# SAM3X-MCU.net
KiCad netlist of a schematic drawn in Altium Designer
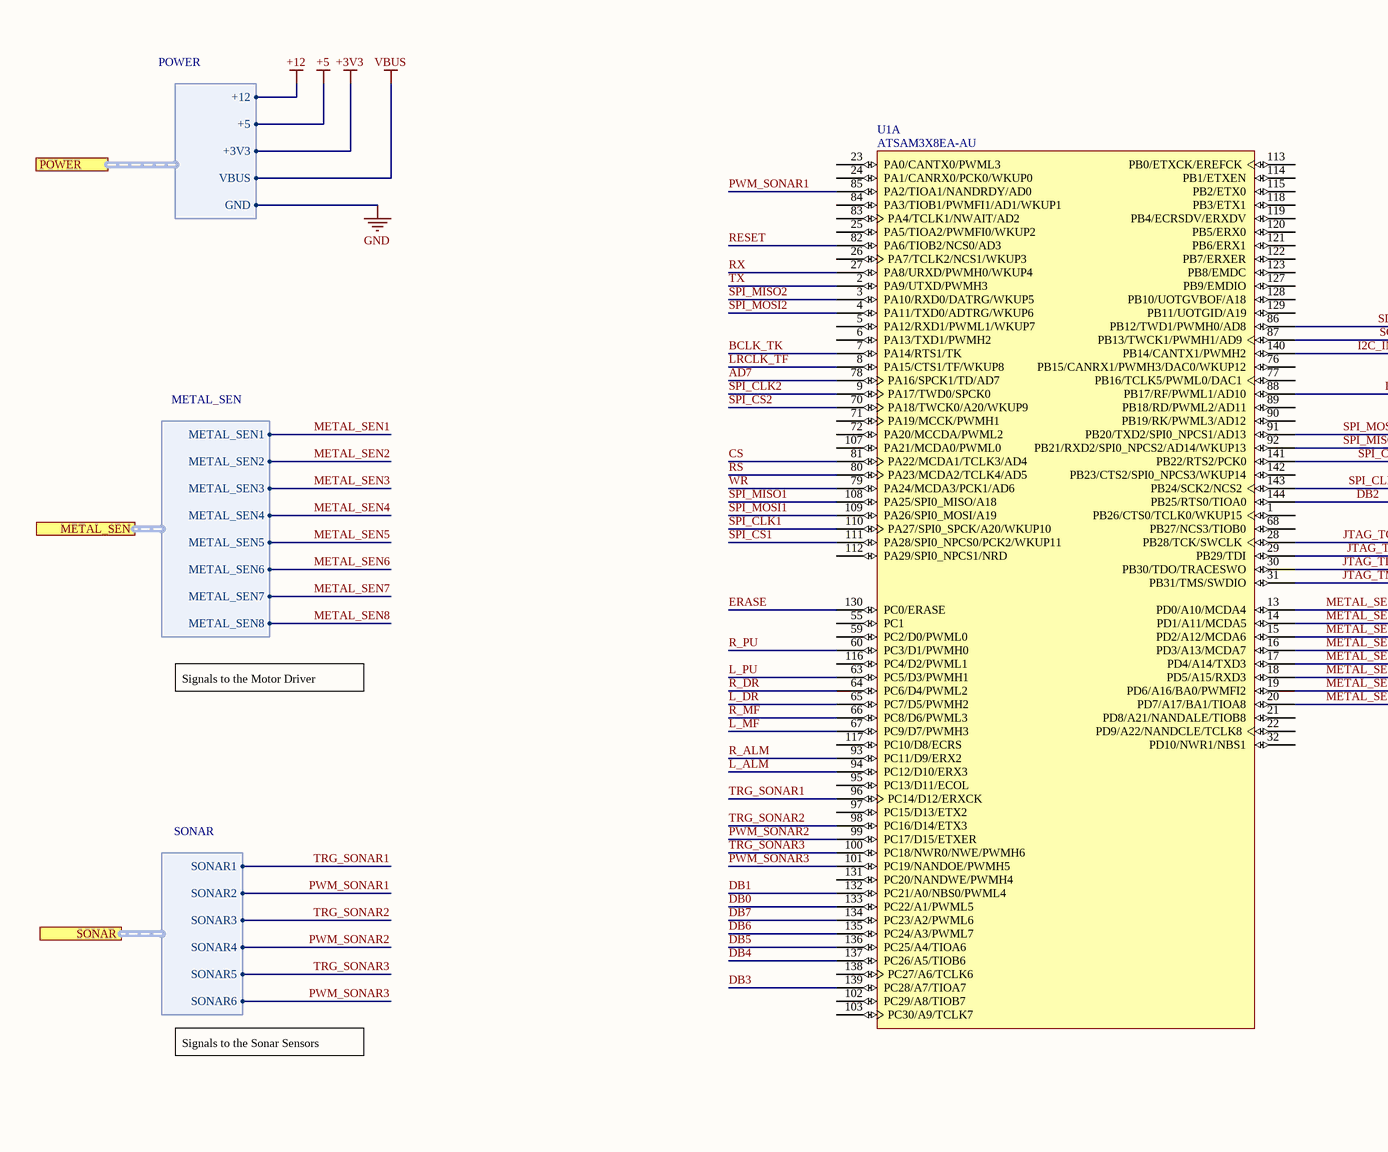
[diagram p0: SAM3X-MCU.SchDoc, left]
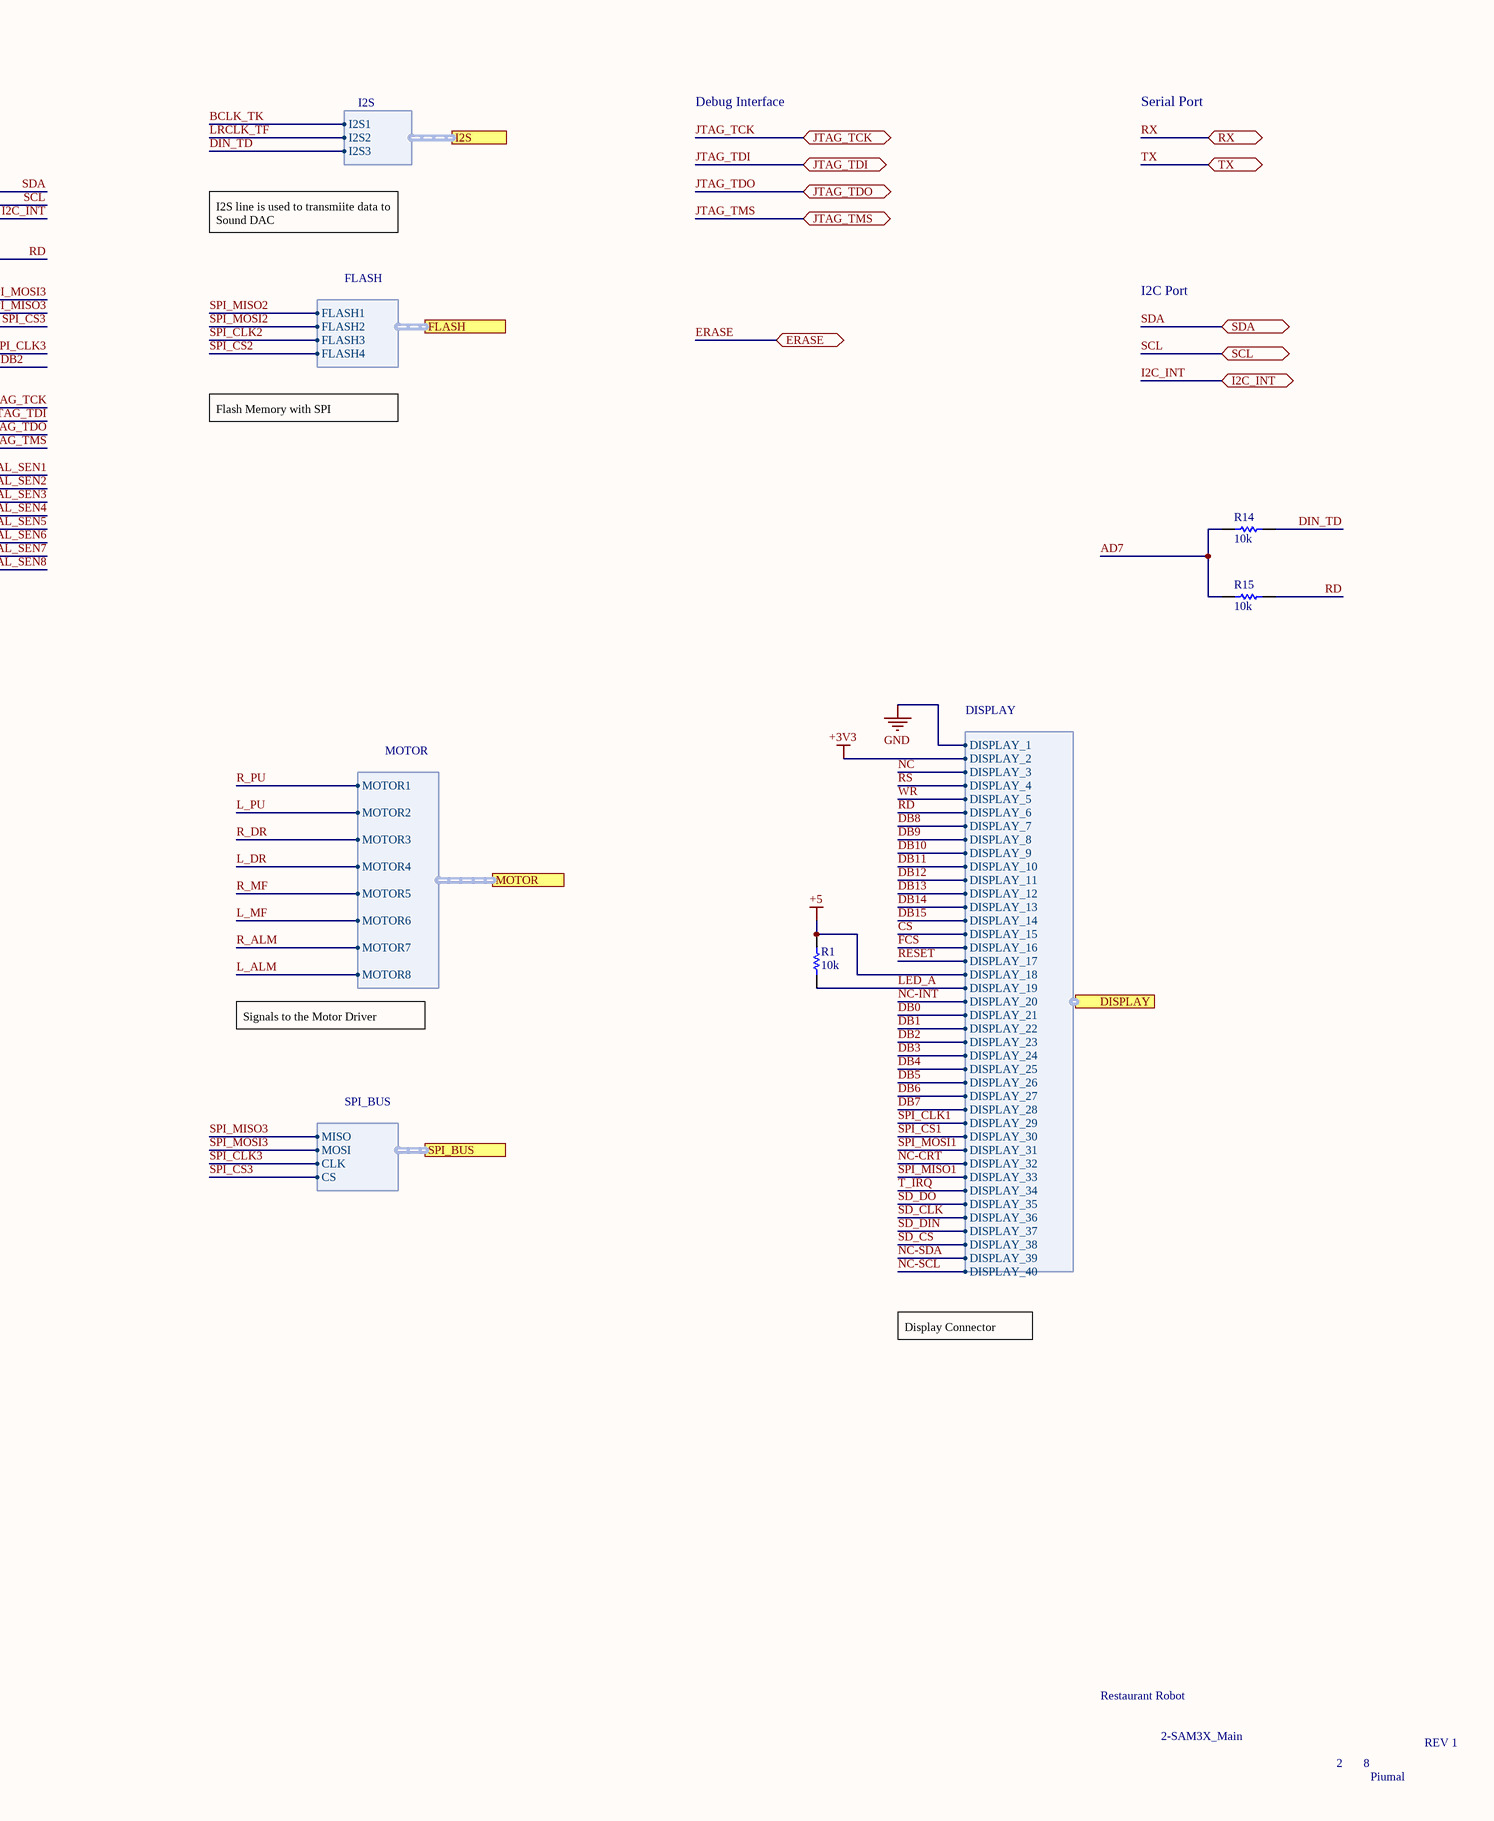
[diagram p1: SAM3X-MCU.SchDoc, right]

(export (version "E")
  (design (tool "Eeschema 10.0.6"))
  (components
    (comp (ref "R1")
      (value "RC0805JR-0710KL")
      (footprint "RESC2013X60X35ML10T20")
      (description "Chip Resistor, 10 KOhm, +/- 5%, 0.125 W, -55 to 155 degC, 0805 (2012 Metric), RoHS, Tape and Reel")
      (fields (field (name "MANUFACTURER") "Yageo") (field (name "RESISTANCE") "10k"))
      (libsource (lib "Altium Content Vault") (part "RES-2"))
    )
    (comp (ref "R14")
      (value "RC0805JR-0710KL")
      (footprint "RESC2013X60X35ML10T20")
      (description "Chip Resistor, 10 KOhm, +/- 5%, 0.125 W, -55 to 155 degC, 0805 (2012 Metric), RoHS, Tape and Reel")
      (fields (field (name "MANUFACTURER") "Yageo") (field (name "RESISTANCE") "10k"))
      (libsource (lib "Altium Content Vault") (part "RES-2"))
    )
    (comp (ref "R15")
      (value "RC0805JR-0710KL")
      (footprint "RESC2013X60X35ML10T20")
      (description "Chip Resistor, 10 KOhm, +/- 5%, 0.125 W, -55 to 155 degC, 0805 (2012 Metric), RoHS, Tape and Reel")
      (fields (field (name "MANUFACTURER") "Yageo") (field (name "RESISTANCE") "10k"))
      (libsource (lib "Altium Content Vault") (part "RES-2"))
    )
    (comp (ref "U1")
      (value "ATSAM3X8EA-AU")
      (footprint "LQFP144_M")
      (fields (field (name "MANUFACTURER") "Atmel"))
      (libsource (lib "Altium Content Vault") (part "ATML-ATSAM3X-LQFP-144"))
    )
  )
  (nets
    (net (code "10") (name "+5") (class "Default")
      (node (ref "R1") (pin "2") (pinfunction "2_2") (pintype "passive"))
    )
    (net (code "12") (name "/AD7") (class "Default")
      (node (ref "R14") (pin "2") (pinfunction "2_2") (pintype "passive"))
      (node (ref "R15") (pin "2") (pinfunction "2_2") (pintype "passive"))
      (node (ref "U1") (pin "78") (pinfunction "PA16/SPCK1/TD/AD7_78") (pintype "bidirectional"))
    )
    (net (code "13") (name "/BCLK_TK") (class "Default")
      (node (ref "U1") (pin "7") (pinfunction "PA14/RTS1/TK_7") (pintype "bidirectional"))
    )
    (net (code "14") (name "/CS") (class "Default")
      (node (ref "U1") (pin "81") (pinfunction "PA22/MCDA1/TCLK3/AD4_81") (pintype "bidirectional"))
    )
    (net (code "15") (name "/DB0") (class "Default")
      (node (ref "U1") (pin "133") (pinfunction "PC22/A1/PWML5_133") (pintype "bidirectional"))
    )
    (net (code "16") (name "/DB1") (class "Default")
      (node (ref "U1") (pin "132") (pinfunction "PC21/A0/NBS0/PWML4_132") (pintype "bidirectional"))
    )
    (net (code "17") (name "/DB2") (class "Default")
      (node (ref "U1") (pin "144") (pinfunction "PB25/RTS0/TIOA0_144") (pintype "bidirectional"))
    )
    (net (code "18") (name "/DB3") (class "Default")
      (node (ref "U1") (pin "139") (pinfunction "PC28/A7/TIOA7_139") (pintype "bidirectional"))
    )
    (net (code "19") (name "/DB4") (class "Default")
      (node (ref "U1") (pin "137") (pinfunction "PC26/A5/TIOB6_137") (pintype "bidirectional"))
    )
    (net (code "20") (name "/DB5") (class "Default")
      (node (ref "U1") (pin "136") (pinfunction "PC25/A4/TIOA6_136") (pintype "bidirectional"))
    )
    (net (code "21") (name "/DB6") (class "Default")
      (node (ref "U1") (pin "135") (pinfunction "PC24/A3/PWML7_135") (pintype "bidirectional"))
    )
    (net (code "22") (name "/DB7") (class "Default")
      (node (ref "U1") (pin "134") (pinfunction "PC23/A2/PWML6_134") (pintype "bidirectional"))
    )
    (net (code "31") (name "/DIN_TD") (class "Default")
      (node (ref "R14") (pin "1") (pinfunction "1_1") (pintype "passive"))
    )
    (net (code "32") (name "/ERASE") (class "Default")
      (node (ref "U1") (pin "130") (pinfunction "PC0/ERASE_130") (pintype "bidirectional"))
    )
    (net (code "34") (name "/I2C_INT") (class "Default")
      (node (ref "U1") (pin "140") (pinfunction "PB14/CANTX1/PWMH2_140") (pintype "bidirectional"))
    )
    (net (code "35") (name "/JTAG_TCK") (class "Default")
      (node (ref "U1") (pin "28") (pinfunction "PB28/TCK/SWCLK_28") (pintype "bidirectional"))
    )
    (net (code "36") (name "/JTAG_TDI") (class "Default")
      (node (ref "U1") (pin "29") (pinfunction "PB29/TDI_29") (pintype "bidirectional"))
    )
    (net (code "37") (name "/JTAG_TDO") (class "Default")
      (node (ref "U1") (pin "30") (pinfunction "PB30/TDO/TRACESWO_30") (pintype "bidirectional"))
    )
    (net (code "38") (name "/JTAG_TMS") (class "Default")
      (node (ref "U1") (pin "31") (pinfunction "PB31/TMS/SWDIO_31") (pintype "bidirectional"))
    )
    (net (code "39") (name "/LED_A") (class "Default")
      (node (ref "R1") (pin "1") (pinfunction "1_1") (pintype "passive"))
    )
    (net (code "40") (name "/LRCLK_TF") (class "Default")
      (node (ref "U1") (pin "8") (pinfunction "PA15/CTS1/TF/WKUP8_8") (pintype "bidirectional"))
    )
    (net (code "41") (name "/L_ALM") (class "Default")
      (node (ref "U1") (pin "94") (pinfunction "PC12/D10/ERX3_94") (pintype "bidirectional"))
    )
    (net (code "42") (name "/L_DR") (class "Default")
      (node (ref "U1") (pin "65") (pinfunction "PC7/D5/PWMH2_65") (pintype "bidirectional"))
    )
    (net (code "43") (name "/L_MF") (class "Default")
      (node (ref "U1") (pin "67") (pinfunction "PC9/D7/PWMH3_67") (pintype "bidirectional"))
    )
    (net (code "44") (name "/L_PU") (class "Default")
      (node (ref "U1") (pin "63") (pinfunction "PC5/D3/PWMH1_63") (pintype "bidirectional"))
    )
    (net (code "45") (name "/METAL_SEN1") (class "Default")
      (node (ref "U1") (pin "13") (pinfunction "PD0/A10/MCDA4_13") (pintype "bidirectional"))
    )
    (net (code "46") (name "/METAL_SEN2") (class "Default")
      (node (ref "U1") (pin "14") (pinfunction "PD1/A11/MCDA5_14") (pintype "bidirectional"))
    )
    (net (code "47") (name "/METAL_SEN3") (class "Default")
      (node (ref "U1") (pin "15") (pinfunction "PD2/A12/MCDA6_15") (pintype "bidirectional"))
    )
    (net (code "48") (name "/METAL_SEN4") (class "Default")
      (node (ref "U1") (pin "16") (pinfunction "PD3/A13/MCDA7_16") (pintype "bidirectional"))
    )
    (net (code "49") (name "/METAL_SEN5") (class "Default")
      (node (ref "U1") (pin "17") (pinfunction "PD4/A14/TXD3_17") (pintype "bidirectional"))
    )
    (net (code "50") (name "/METAL_SEN6") (class "Default")
      (node (ref "U1") (pin "18") (pinfunction "PD5/A15/RXD3_18") (pintype "bidirectional"))
    )
    (net (code "51") (name "/METAL_SEN7") (class "Default")
      (node (ref "U1") (pin "19") (pinfunction "PD6/A16/BA0/PWMFI2_19") (pintype "bidirectional"))
    )
    (net (code "52") (name "/METAL_SEN8") (class "Default")
      (node (ref "U1") (pin "20") (pinfunction "PD7/A17/BA1/TIOA8_20") (pintype "bidirectional"))
    )
    (net (code "58") (name "/PWM_SONAR1") (class "Default")
      (node (ref "U1") (pin "85") (pinfunction "PA2/TIOA1/NANDRDY/AD0_85") (pintype "bidirectional"))
    )
    (net (code "59") (name "/PWM_SONAR2") (class "Default")
      (node (ref "U1") (pin "99") (pinfunction "PC17/D15/ETXER_99") (pintype "bidirectional"))
    )
    (net (code "60") (name "/PWM_SONAR3") (class "Default")
      (node (ref "U1") (pin "101") (pinfunction "PC19/NANDOE/PWMH5_101") (pintype "bidirectional"))
    )
    (net (code "61") (name "/RD") (class "Default")
      (node (ref "R15") (pin "1") (pinfunction "1_1") (pintype "passive"))
      (node (ref "U1") (pin "88") (pinfunction "PB17/RF/PWML1/AD10_88") (pintype "bidirectional"))
    )
    (net (code "62") (name "/RESET") (class "Default")
      (node (ref "U1") (pin "82") (pinfunction "PA6/TIOB2/NCS0/AD3_82") (pintype "bidirectional"))
    )
    (net (code "63") (name "/RS") (class "Default")
      (node (ref "U1") (pin "80") (pinfunction "PA23/MCDA2/TCLK4/AD5_80") (pintype "bidirectional"))
    )
    (net (code "64") (name "/RX") (class "Default")
      (node (ref "U1") (pin "27") (pinfunction "PA8/URXD/PWMH0/WKUP4_27") (pintype "bidirectional"))
    )
    (net (code "65") (name "/R_ALM") (class "Default")
      (node (ref "U1") (pin "93") (pinfunction "PC11/D9/ERX2_93") (pintype "bidirectional"))
    )
    (net (code "66") (name "/R_DR") (class "Default")
      (node (ref "U1") (pin "64") (pinfunction "PC6/D4/PWML2_64") (pintype "bidirectional"))
    )
    (net (code "67") (name "/R_MF") (class "Default")
      (node (ref "U1") (pin "66") (pinfunction "PC8/D6/PWML3_66") (pintype "bidirectional"))
    )
    (net (code "68") (name "/R_PU") (class "Default")
      (node (ref "U1") (pin "60") (pinfunction "PC3/D1/PWMH0_60") (pintype "bidirectional"))
    )
    (net (code "69") (name "/SCL") (class "Default")
      (node (ref "U1") (pin "87") (pinfunction "PB13/TWCK1/PWMH1/AD9_87") (pintype "bidirectional"))
    )
    (net (code "70") (name "/SDA") (class "Default")
      (node (ref "U1") (pin "86") (pinfunction "PB12/TWD1/PWMH0/AD8_86") (pintype "bidirectional"))
    )
    (net (code "75") (name "/SPI_CLK1") (class "Default")
      (node (ref "U1") (pin "110") (pinfunction "PA27/SPI0_SPCK/A20/WKUP10_110") (pintype "bidirectional"))
    )
    (net (code "76") (name "/SPI_CLK2") (class "Default")
      (node (ref "U1") (pin "9") (pinfunction "PA17/TWD0/SPCK0_9") (pintype "bidirectional"))
    )
    (net (code "77") (name "/SPI_CLK3") (class "Default")
      (node (ref "U1") (pin "143") (pinfunction "PB24/SCK2/NCS2_143") (pintype "bidirectional"))
    )
    (net (code "78") (name "/SPI_CS1") (class "Default")
      (node (ref "U1") (pin "111") (pinfunction "PA28/SPI0_NPCS0/PCK2/WKUP11_111") (pintype "bidirectional"))
    )
    (net (code "79") (name "/SPI_CS2") (class "Default")
      (node (ref "U1") (pin "70") (pinfunction "PA18/TWCK0/A20/WKUP9_70") (pintype "bidirectional"))
    )
    (net (code "80") (name "/SPI_CS3") (class "Default")
      (node (ref "U1") (pin "141") (pinfunction "PB22/RTS2/PCK0_141") (pintype "bidirectional"))
    )
    (net (code "81") (name "/SPI_MISO1") (class "Default")
      (node (ref "U1") (pin "108") (pinfunction "PA25/SPI0_MISO/A18_108") (pintype "bidirectional"))
    )
    (net (code "82") (name "/SPI_MISO2") (class "Default")
      (node (ref "U1") (pin "3") (pinfunction "PA10/RXD0/DATRG/WKUP5_3") (pintype "bidirectional"))
    )
    (net (code "83") (name "/SPI_MISO3") (class "Default")
      (node (ref "U1") (pin "92") (pinfunction "PB21/RXD2/SPI0_NPCS2/AD14/WKUP13_92") (pintype "bidirectional"))
    )
    (net (code "84") (name "/SPI_MOSI1") (class "Default")
      (node (ref "U1") (pin "109") (pinfunction "PA26/SPI0_MOSI/A19_109") (pintype "bidirectional"))
    )
    (net (code "85") (name "/SPI_MOSI2") (class "Default")
      (node (ref "U1") (pin "4") (pinfunction "PA11/TXD0/ADTRG/WKUP6_4") (pintype "bidirectional"))
    )
    (net (code "86") (name "/SPI_MOSI3") (class "Default")
      (node (ref "U1") (pin "91") (pinfunction "PB20/TXD2/SPI0_NPCS1/AD13_91") (pintype "bidirectional"))
    )
    (net (code "87") (name "/TRG_SONAR1") (class "Default")
      (node (ref "U1") (pin "96") (pinfunction "PC14/D12/ERXCK_96") (pintype "bidirectional"))
    )
    (net (code "88") (name "/TRG_SONAR2") (class "Default")
      (node (ref "U1") (pin "98") (pinfunction "PC16/D14/ETX3_98") (pintype "bidirectional"))
    )
    (net (code "89") (name "/TRG_SONAR3") (class "Default")
      (node (ref "U1") (pin "100") (pinfunction "PC18/NWR0/NWE/PWMH6_100") (pintype "bidirectional"))
    )
    (net (code "90") (name "/TX") (class "Default")
      (node (ref "U1") (pin "2") (pinfunction "PA9/UTXD/PWMH3_2") (pintype "bidirectional"))
    )
    (net (code "92") (name "/WR") (class "Default")
      (node (ref "U1") (pin "79") (pinfunction "PA24/MCDA3/PCK1/AD6_79") (pintype "bidirectional"))
    )
    (net (code "103") (name "unconnected-(U1A-PA0{slash}CANTX0{slash}PWML3-Pad23)") (class "Default")
      (node (ref "U1") (pin "23") (pinfunction "PA0/CANTX0/PWML3_23") (pintype "bidirectional"))
    )
    (net (code "104") (name "unconnected-(U1A-PA1{slash}CANRX0{slash}PCK0{slash}WKUP0-Pad24)") (class "Default")
      (node (ref "U1") (pin "24") (pinfunction "PA1/CANRX0/PCK0/WKUP0_24") (pintype "bidirectional"))
    )
    (net (code "105") (name "unconnected-(U1A-PA3{slash}TIOB1{slash}PWMFI1{slash}AD1{slash}WKUP1-Pad84)") (class "Default")
      (node (ref "U1") (pin "84") (pinfunction "PA3/TIOB1/PWMFI1/AD1/WKUP1_84") (pintype "bidirectional"))
    )
    (net (code "106") (name "unconnected-(U1A-PA4{slash}TCLK1{slash}NWAIT{slash}AD2-Pad83)") (class "Default")
      (node (ref "U1") (pin "83") (pinfunction "PA4/TCLK1/NWAIT/AD2_83") (pintype "bidirectional"))
    )
    (net (code "107") (name "unconnected-(U1A-PA5{slash}TIOA2{slash}PWMFI0{slash}WKUP2-Pad25)") (class "Default")
      (node (ref "U1") (pin "25") (pinfunction "PA5/TIOA2/PWMFI0/WKUP2_25") (pintype "bidirectional"))
    )
    (net (code "108") (name "unconnected-(U1A-PA7{slash}TCLK2{slash}NCS1{slash}WKUP3-Pad26)") (class "Default")
      (node (ref "U1") (pin "26") (pinfunction "PA7/TCLK2/NCS1/WKUP3_26") (pintype "bidirectional"))
    )
    (net (code "109") (name "unconnected-(U1A-PA12{slash}RXD1{slash}PWML1{slash}WKUP7-Pad5)") (class "Default")
      (node (ref "U1") (pin "5") (pinfunction "PA12/RXD1/PWML1/WKUP7_5") (pintype "bidirectional"))
    )
    (net (code "110") (name "unconnected-(U1A-PA13{slash}TXD1{slash}PWMH2-Pad6)") (class "Default")
      (node (ref "U1") (pin "6") (pinfunction "PA13/TXD1/PWMH2_6") (pintype "bidirectional"))
    )
    (net (code "111") (name "unconnected-(U1A-PA19{slash}MCCK{slash}PWMH1-Pad71)") (class "Default")
      (node (ref "U1") (pin "71") (pinfunction "PA19/MCCK/PWMH1_71") (pintype "bidirectional"))
    )
    (net (code "112") (name "unconnected-(U1A-PA20{slash}MCCDA{slash}PWML2-Pad72)") (class "Default")
      (node (ref "U1") (pin "72") (pinfunction "PA20/MCCDA/PWML2_72") (pintype "bidirectional"))
    )
    (net (code "113") (name "unconnected-(U1A-PA21{slash}MCDA0{slash}PWML0-Pad107)") (class "Default")
      (node (ref "U1") (pin "107") (pinfunction "PA21/MCDA0/PWML0_107") (pintype "bidirectional"))
    )
    (net (code "114") (name "unconnected-(U1A-PA29{slash}SPI0_NPCS1{slash}NRD-Pad112)") (class "Default")
      (node (ref "U1") (pin "112") (pinfunction "PA29/SPI0_NPCS1/NRD_112") (pintype "bidirectional"))
    )
    (net (code "115") (name "unconnected-(U1A-PB0{slash}ETXCK{slash}EREFCK-Pad113)") (class "Default")
      (node (ref "U1") (pin "113") (pinfunction "PB0/ETXCK/EREFCK_113") (pintype "bidirectional"))
    )
    (net (code "116") (name "unconnected-(U1A-PB1{slash}ETXEN-Pad114)") (class "Default")
      (node (ref "U1") (pin "114") (pinfunction "PB1/ETXEN_114") (pintype "bidirectional"))
    )
    (net (code "117") (name "unconnected-(U1A-PB2{slash}ETX0-Pad115)") (class "Default")
      (node (ref "U1") (pin "115") (pinfunction "PB2/ETX0_115") (pintype "bidirectional"))
    )
    (net (code "118") (name "unconnected-(U1A-PB3{slash}ETX1-Pad118)") (class "Default")
      (node (ref "U1") (pin "118") (pinfunction "PB3/ETX1_118") (pintype "bidirectional"))
    )
    (net (code "119") (name "unconnected-(U1A-PB4{slash}ECRSDV{slash}ERXDV-Pad119)") (class "Default")
      (node (ref "U1") (pin "119") (pinfunction "PB4/ECRSDV/ERXDV_119") (pintype "bidirectional"))
    )
    (net (code "120") (name "unconnected-(U1A-PB5{slash}ERX0-Pad120)") (class "Default")
      (node (ref "U1") (pin "120") (pinfunction "PB5/ERX0_120") (pintype "bidirectional"))
    )
    (net (code "121") (name "unconnected-(U1A-PB6{slash}ERX1-Pad121)") (class "Default")
      (node (ref "U1") (pin "121") (pinfunction "PB6/ERX1_121") (pintype "bidirectional"))
    )
    (net (code "122") (name "unconnected-(U1A-PB7{slash}ERXER-Pad122)") (class "Default")
      (node (ref "U1") (pin "122") (pinfunction "PB7/ERXER_122") (pintype "bidirectional"))
    )
    (net (code "123") (name "unconnected-(U1A-PB8{slash}EMDC-Pad123)") (class "Default")
      (node (ref "U1") (pin "123") (pinfunction "PB8/EMDC_123") (pintype "bidirectional"))
    )
    (net (code "124") (name "unconnected-(U1A-PB9{slash}EMDIO-Pad127)") (class "Default")
      (node (ref "U1") (pin "127") (pinfunction "PB9/EMDIO_127") (pintype "bidirectional"))
    )
    (net (code "125") (name "unconnected-(U1A-PB10{slash}UOTGVBOF{slash}A18-Pad128)") (class "Default")
      (node (ref "U1") (pin "128") (pinfunction "PB10/UOTGVBOF/A18_128") (pintype "bidirectional"))
    )
    (net (code "126") (name "unconnected-(U1A-PB11{slash}UOTGID{slash}A19-Pad129)") (class "Default")
      (node (ref "U1") (pin "129") (pinfunction "PB11/UOTGID/A19_129") (pintype "bidirectional"))
    )
    (net (code "127") (name "unconnected-(U1A-PB15{slash}CANRX1{slash}PWMH3{slash}DAC0{slash}WKUP12-Pad76)") (class "Default")
      (node (ref "U1") (pin "76") (pinfunction "PB15/CANRX1/PWMH3/DAC0/WKUP12_76") (pintype "bidirectional"))
    )
    (net (code "128") (name "unconnected-(U1A-PB16{slash}TCLK5{slash}PWML0{slash}DAC1-Pad77)") (class "Default")
      (node (ref "U1") (pin "77") (pinfunction "PB16/TCLK5/PWML0/DAC1_77") (pintype "bidirectional"))
    )
    (net (code "129") (name "unconnected-(U1A-PB18{slash}RD{slash}PWML2{slash}AD11-Pad89)") (class "Default")
      (node (ref "U1") (pin "89") (pinfunction "PB18/RD/PWML2/AD11_89") (pintype "bidirectional"))
    )
    (net (code "130") (name "unconnected-(U1A-PB19{slash}RK{slash}PWML3{slash}AD12-Pad90)") (class "Default")
      (node (ref "U1") (pin "90") (pinfunction "PB19/RK/PWML3/AD12_90") (pintype "bidirectional"))
    )
    (net (code "131") (name "unconnected-(U1A-PB23{slash}CTS2{slash}SPI0_NPCS3{slash}WKUP14-Pad142)") (class "Default")
      (node (ref "U1") (pin "142") (pinfunction "PB23/CTS2/SPI0_NPCS3/WKUP14_142") (pintype "bidirectional"))
    )
    (net (code "132") (name "unconnected-(U1A-PB26{slash}CTS0{slash}TCLK0{slash}WKUP15-Pad1)") (class "Default")
      (node (ref "U1") (pin "1") (pinfunction "PB26/CTS0/TCLK0/WKUP15_1") (pintype "bidirectional"))
    )
    (net (code "133") (name "unconnected-(U1A-PB27{slash}NCS3{slash}TIOB0-Pad68)") (class "Default")
      (node (ref "U1") (pin "68") (pinfunction "PB27/NCS3/TIOB0_68") (pintype "bidirectional"))
    )
    (net (code "134") (name "unconnected-(U1A-PC1-Pad55)") (class "Default")
      (node (ref "U1") (pin "55") (pinfunction "PC1_55") (pintype "bidirectional"))
    )
    (net (code "135") (name "unconnected-(U1A-PC2{slash}D0{slash}PWML0-Pad59)") (class "Default")
      (node (ref "U1") (pin "59") (pinfunction "PC2/D0/PWML0_59") (pintype "bidirectional"))
    )
    (net (code "136") (name "unconnected-(U1A-PC4{slash}D2{slash}PWML1-Pad116)") (class "Default")
      (node (ref "U1") (pin "116") (pinfunction "PC4/D2/PWML1_116") (pintype "bidirectional"))
    )
    (net (code "137") (name "unconnected-(U1A-PC10{slash}D8{slash}ECRS-Pad117)") (class "Default")
      (node (ref "U1") (pin "117") (pinfunction "PC10/D8/ECRS_117") (pintype "bidirectional"))
    )
    (net (code "138") (name "unconnected-(U1A-PC13{slash}D11{slash}ECOL-Pad95)") (class "Default")
      (node (ref "U1") (pin "95") (pinfunction "PC13/D11/ECOL_95") (pintype "bidirectional"))
    )
    (net (code "139") (name "unconnected-(U1A-PC15{slash}D13{slash}ETX2-Pad97)") (class "Default")
      (node (ref "U1") (pin "97") (pinfunction "PC15/D13/ETX2_97") (pintype "bidirectional"))
    )
    (net (code "140") (name "unconnected-(U1A-PC20{slash}NANDWE{slash}PWMH4-Pad131)") (class "Default")
      (node (ref "U1") (pin "131") (pinfunction "PC20/NANDWE/PWMH4_131") (pintype "bidirectional"))
    )
    (net (code "141") (name "unconnected-(U1A-PC27{slash}A6{slash}TCLK6-Pad138)") (class "Default")
      (node (ref "U1") (pin "138") (pinfunction "PC27/A6/TCLK6_138") (pintype "bidirectional"))
    )
    (net (code "142") (name "unconnected-(U1A-PC29{slash}A8{slash}TIOB7-Pad102)") (class "Default")
      (node (ref "U1") (pin "102") (pinfunction "PC29/A8/TIOB7_102") (pintype "bidirectional"))
    )
    (net (code "143") (name "unconnected-(U1A-PC30{slash}A9{slash}TCLK7-Pad103)") (class "Default")
      (node (ref "U1") (pin "103") (pinfunction "PC30/A9/TCLK7_103") (pintype "bidirectional"))
    )
    (net (code "144") (name "unconnected-(U1A-PD8{slash}A21{slash}NANDALE{slash}TIOB8-Pad21)") (class "Default")
      (node (ref "U1") (pin "21") (pinfunction "PD8/A21/NANDALE/TIOB8_21") (pintype "bidirectional"))
    )
    (net (code "145") (name "unconnected-(U1A-PD9{slash}A22{slash}NANDCLE{slash}TCLK8-Pad22)") (class "Default")
      (node (ref "U1") (pin "22") (pinfunction "PD9/A22/NANDCLE/TCLK8_22") (pintype "bidirectional"))
    )
    (net (code "146") (name "unconnected-(U1A-PD10{slash}NWR1{slash}NBS1-Pad32)") (class "Default")
      (node (ref "U1") (pin "32") (pinfunction "PD10/NWR1/NBS1_32") (pintype "bidirectional"))
    )
  )
)
